# Releais-Karte-A_00_01.net
KiCad netlist of a schematic drawn in EasyEDA
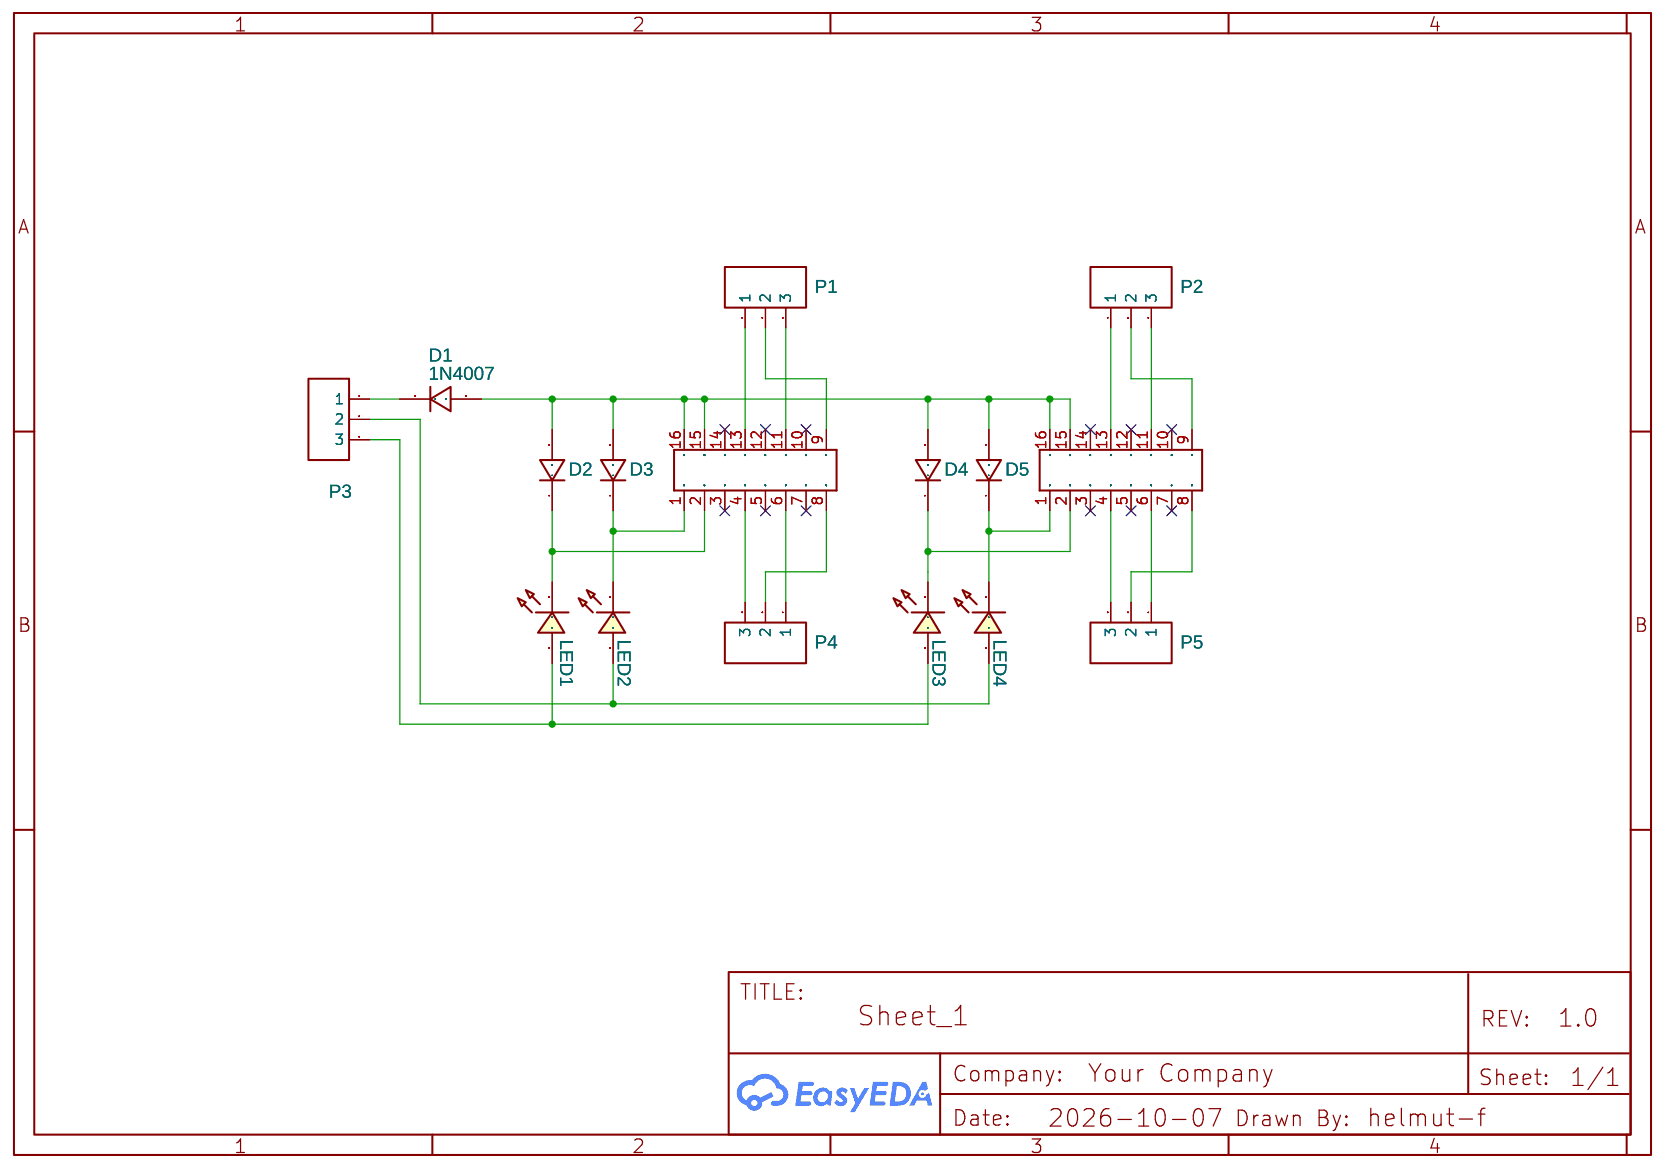
[diagram p0: schematic sheet]

(export (version "E")
  (design (tool "Eeschema 10.0.6"))
  (components
    (comp (ref "D1")
      (value "1N4007")
      (fields (field (name "Manufacturer") "SEMTECH"))
      (libsource (lib "") (part "1N4007_1"))
    )
    (comp (ref "D2")
      (value "1N4007")
      (fields (field (name "Manufacturer") "SEMTECH"))
      (libsource (lib "") (part "1N4007"))
    )
    (comp (ref "D3")
      (value "1N4007")
      (fields (field (name "Manufacturer") "SEMTECH"))
      (libsource (lib "") (part "1N4007"))
    )
    (comp (ref "D4")
      (value "1N4007")
      (fields (field (name "Manufacturer") "SEMTECH"))
      (libsource (lib "") (part "1N4007"))
    )
    (comp (ref "D5")
      (value "1N4007")
      (fields (field (name "Manufacturer") "SEMTECH"))
      (libsource (lib "") (part "1N4007"))
    )
    (comp (ref "J1")
      (value "DIP-IC-SOCKET(2X8P-2.54) 16 pin")
      (libsource (lib "") (part "DIP-IC-SOCKET(2X8P-2.54) 16 pin"))
    )
    (comp (ref "J2")
      (value "DIP-IC-SOCKET(2X8P-2.54) 16 pin")
      (libsource (lib "") (part "DIP-IC-SOCKET(2X8P-2.54) 16 pin"))
    )
    (comp (ref "LED1")
      (value "LED-TH-3mm_R")
      (fields
        (field (name "Manufacturer Part") "204-10SDRD/S530-A3-L")
        (field (name "Manufacturer") "EVERLIGHT(台湾亿光)")
      )
      (libsource (lib "") (part "LED-TH-3mm_R"))
    )
    (comp (ref "LED2")
      (value "LED-TH-3mm_G")
      (fields
        (field (name "Manufacturer Part") "204-10SYGD/S530-E3")
        (field (name "Manufacturer") "EVERLIGHT(台湾亿光)")
      )
      (libsource (lib "") (part "LED-TH-3mm_G"))
    )
    (comp (ref "LED3")
      (value "LED-TH-3mm_R")
      (fields
        (field (name "Manufacturer Part") "204-10SDRD/S530-A3-L")
        (field (name "Manufacturer") "EVERLIGHT(台湾亿光)")
      )
      (libsource (lib "") (part "LED-TH-3mm_R"))
    )
    (comp (ref "LED4")
      (value "LED-TH-3mm_G")
      (fields
        (field (name "Manufacturer Part") "204-10SYGD/S530-E3")
        (field (name "Manufacturer") "EVERLIGHT(台湾亿光)")
      )
      (libsource (lib "") (part "LED-TH-3mm_G"))
    )
    (comp (ref "P1") (value "CONN-TH_3P-P5.08") (libsource (lib "") (part "CONN-TH_3P-P5.08_2")))
    (comp (ref "P2") (value "CONN-TH_3P-P5.08") (libsource (lib "") (part "CONN-TH_3P-P5.08_2")))
    (comp (ref "P3") (value "CONN-TH_3P-P5.08") (libsource (lib "") (part "CONN-TH_3P-P5.08_1")))
    (comp (ref "P4") (value "CONN-TH_3P-P5.08") (libsource (lib "") (part "CONN-TH_3P-P5.08")))
    (comp (ref "P5") (value "CONN-TH_3P-P5.08") (libsource (lib "") (part "CONN-TH_3P-P5.08")))
  )
  (nets
    (net (code "1") (name "Net-(D1-Pad1)") (class "Default")
      (node (ref "D1") (pin "1") (pinfunction "1_1") (pintype "unspecified"))
      (node (ref "P3") (pin "1") (pinfunction "1_1") (pintype "unspecified"))
    )
    (net (code "2") (name "Net-(J1-P$1)") (class "Default")
      (node (ref "D3") (pin "1") (pinfunction "1_1") (pintype "unspecified"))
      (node (ref "J1") (pin "1") (pinfunction "P$1_1") (pintype "unspecified"))
      (node (ref "LED2") (pin "2") (pinfunction "2_2") (pintype "unspecified"))
    )
    (net (code "3") (name "Net-(J1-P$2)") (class "Default")
      (node (ref "D2") (pin "1") (pinfunction "1_1") (pintype "unspecified"))
      (node (ref "J1") (pin "2") (pinfunction "P$2_2") (pintype "unspecified"))
      (node (ref "LED1") (pin "2") (pinfunction "2_2") (pintype "unspecified"))
    )
    (net (code "4") (name "Net-(J1-P$4)") (class "Default")
      (node (ref "J1") (pin "4") (pinfunction "P$4_4") (pintype "unspecified"))
      (node (ref "P4") (pin "3") (pinfunction "3_3") (pintype "unspecified"))
    )
    (net (code "5") (name "Net-(J1-P$6)") (class "Default")
      (node (ref "J1") (pin "6") (pinfunction "P$6_6") (pintype "unspecified"))
      (node (ref "P4") (pin "1") (pinfunction "1_1") (pintype "unspecified"))
    )
    (net (code "6") (name "Net-(J1-P$8)") (class "Default")
      (node (ref "J1") (pin "8") (pinfunction "P$8_8") (pintype "unspecified"))
      (node (ref "P4") (pin "2") (pinfunction "2_2") (pintype "unspecified"))
    )
    (net (code "7") (name "Net-(J1-P$9)") (class "Default")
      (node (ref "J1") (pin "9") (pinfunction "P$9_9") (pintype "unspecified"))
      (node (ref "P1") (pin "2") (pinfunction "2_2") (pintype "unspecified"))
    )
    (net (code "8") (name "Net-(J1-P$11)") (class "Default")
      (node (ref "J1") (pin "11") (pinfunction "P$11_11") (pintype "unspecified"))
      (node (ref "P1") (pin "3") (pinfunction "3_3") (pintype "unspecified"))
    )
    (net (code "9") (name "Net-(J1-P$13)") (class "Default")
      (node (ref "J1") (pin "13") (pinfunction "P$13_13") (pintype "unspecified"))
      (node (ref "P1") (pin "1") (pinfunction "1_1") (pintype "unspecified"))
    )
    (net (code "10") (name "Net-(J1-P$15)") (class "Default")
      (node (ref "D1") (pin "2") (pinfunction "2_2") (pintype "unspecified"))
      (node (ref "D2") (pin "2") (pinfunction "2_2") (pintype "unspecified"))
      (node (ref "D3") (pin "2") (pinfunction "2_2") (pintype "unspecified"))
      (node (ref "D4") (pin "2") (pinfunction "2_2") (pintype "unspecified"))
      (node (ref "D5") (pin "2") (pinfunction "2_2") (pintype "unspecified"))
      (node (ref "J1") (pin "15") (pinfunction "P$15_15") (pintype "unspecified"))
      (node (ref "J1") (pin "16") (pinfunction "P$16_16") (pintype "unspecified"))
      (node (ref "J2") (pin "15") (pinfunction "P$15_15") (pintype "unspecified"))
      (node (ref "J2") (pin "16") (pinfunction "P$16_16") (pintype "unspecified"))
    )
    (net (code "11") (name "Net-(J2-P$1)") (class "Default")
      (node (ref "D5") (pin "1") (pinfunction "1_1") (pintype "unspecified"))
      (node (ref "J2") (pin "1") (pinfunction "P$1_1") (pintype "unspecified"))
      (node (ref "LED4") (pin "2") (pinfunction "2_2") (pintype "unspecified"))
    )
    (net (code "12") (name "Net-(J2-P$2)") (class "Default")
      (node (ref "D4") (pin "1") (pinfunction "1_1") (pintype "unspecified"))
      (node (ref "J2") (pin "2") (pinfunction "P$2_2") (pintype "unspecified"))
      (node (ref "LED3") (pin "2") (pinfunction "2_2") (pintype "unspecified"))
    )
    (net (code "13") (name "Net-(J2-P$4)") (class "Default")
      (node (ref "J2") (pin "4") (pinfunction "P$4_4") (pintype "unspecified"))
      (node (ref "P5") (pin "3") (pinfunction "3_3") (pintype "unspecified"))
    )
    (net (code "14") (name "Net-(J2-P$6)") (class "Default")
      (node (ref "J2") (pin "6") (pinfunction "P$6_6") (pintype "unspecified"))
      (node (ref "P5") (pin "1") (pinfunction "1_1") (pintype "unspecified"))
    )
    (net (code "15") (name "Net-(J2-P$8)") (class "Default")
      (node (ref "J2") (pin "8") (pinfunction "P$8_8") (pintype "unspecified"))
      (node (ref "P5") (pin "2") (pinfunction "2_2") (pintype "unspecified"))
    )
    (net (code "16") (name "Net-(J2-P$9)") (class "Default")
      (node (ref "J2") (pin "9") (pinfunction "P$9_9") (pintype "unspecified"))
      (node (ref "P2") (pin "2") (pinfunction "2_2") (pintype "unspecified"))
    )
    (net (code "17") (name "Net-(J2-P$11)") (class "Default")
      (node (ref "J2") (pin "11") (pinfunction "P$11_11") (pintype "unspecified"))
      (node (ref "P2") (pin "3") (pinfunction "3_3") (pintype "unspecified"))
    )
    (net (code "18") (name "Net-(J2-P$13)") (class "Default")
      (node (ref "J2") (pin "13") (pinfunction "P$13_13") (pintype "unspecified"))
      (node (ref "P2") (pin "1") (pinfunction "1_1") (pintype "unspecified"))
    )
    (net (code "19") (name "Net-(LED1-Pad1)") (class "Default")
      (node (ref "LED1") (pin "1") (pinfunction "1_1") (pintype "unspecified"))
      (node (ref "LED3") (pin "1") (pinfunction "1_1") (pintype "unspecified"))
      (node (ref "P3") (pin "3") (pinfunction "3_3") (pintype "unspecified"))
    )
    (net (code "20") (name "Net-(LED2-Pad1)") (class "Default")
      (node (ref "LED2") (pin "1") (pinfunction "1_1") (pintype "unspecified"))
      (node (ref "LED4") (pin "1") (pinfunction "1_1") (pintype "unspecified"))
      (node (ref "P3") (pin "2") (pinfunction "2_2") (pintype "unspecified"))
    )
    (net (code "21") (name "unconnected-(J1-P$3-Pad3)") (class "Default")
      (node (ref "J1") (pin "3") (pinfunction "P$3_3") (pintype "unspecified+no_connect"))
    )
    (net (code "22") (name "unconnected-(J1-P$5-Pad5)") (class "Default")
      (node (ref "J1") (pin "5") (pinfunction "P$5_5") (pintype "unspecified+no_connect"))
    )
    (net (code "23") (name "unconnected-(J1-P$7-Pad7)") (class "Default")
      (node (ref "J1") (pin "7") (pinfunction "P$7_7") (pintype "unspecified+no_connect"))
    )
    (net (code "24") (name "unconnected-(J1-P$10-Pad10)") (class "Default")
      (node (ref "J1") (pin "10") (pinfunction "P$10_10") (pintype "unspecified+no_connect"))
    )
    (net (code "25") (name "unconnected-(J1-P$12-Pad12)") (class "Default")
      (node (ref "J1") (pin "12") (pinfunction "P$12_12") (pintype "unspecified+no_connect"))
    )
    (net (code "26") (name "unconnected-(J1-P$14-Pad14)") (class "Default")
      (node (ref "J1") (pin "14") (pinfunction "P$14_14") (pintype "unspecified+no_connect"))
    )
    (net (code "27") (name "unconnected-(J2-P$3-Pad3)") (class "Default")
      (node (ref "J2") (pin "3") (pinfunction "P$3_3") (pintype "unspecified+no_connect"))
    )
    (net (code "28") (name "unconnected-(J2-P$5-Pad5)") (class "Default")
      (node (ref "J2") (pin "5") (pinfunction "P$5_5") (pintype "unspecified+no_connect"))
    )
    (net (code "29") (name "unconnected-(J2-P$7-Pad7)") (class "Default")
      (node (ref "J2") (pin "7") (pinfunction "P$7_7") (pintype "unspecified+no_connect"))
    )
    (net (code "30") (name "unconnected-(J2-P$10-Pad10)") (class "Default")
      (node (ref "J2") (pin "10") (pinfunction "P$10_10") (pintype "unspecified+no_connect"))
    )
    (net (code "31") (name "unconnected-(J2-P$12-Pad12)") (class "Default")
      (node (ref "J2") (pin "12") (pinfunction "P$12_12") (pintype "unspecified+no_connect"))
    )
    (net (code "32") (name "unconnected-(J2-P$14-Pad14)") (class "Default")
      (node (ref "J2") (pin "14") (pinfunction "P$14_14") (pintype "unspecified+no_connect"))
    )
  )
)
